# ButtonHighlight.net
KiCad netlist of a schematic drawn in EAGLE
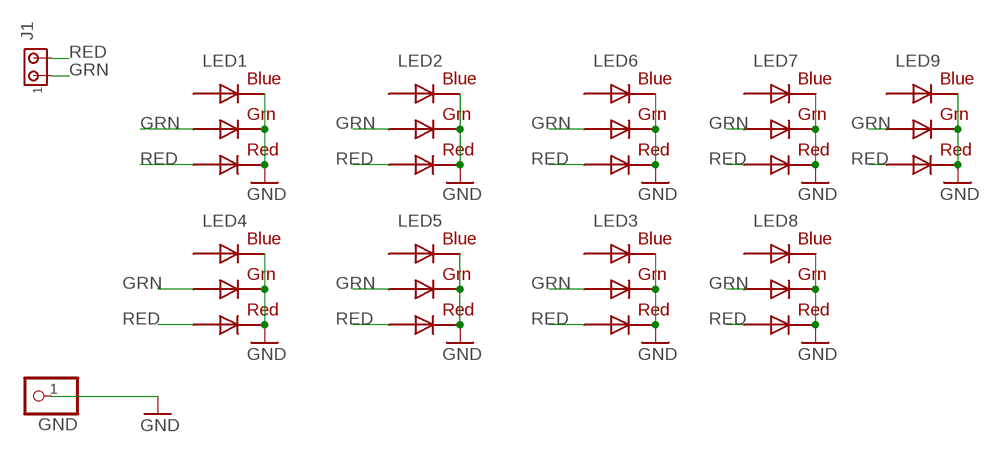
[diagram p0: schematic, sheet 1]

(export (version "E")
  (design (tool "Eeschema 10.0.6"))
  (components
    (comp (ref "GND")
      (value "PINHD-1X1")
      (footprint "eagle-import:1X01")
      (libsource (lib "eagle-import") (part "PINHD-1X1"))
    )
    (comp (ref "J1")
      (value "MTA02-100")
      (footprint "eagle-import:10X02MTA")
      (libsource (lib "eagle-import") (part "MTA02-100"))
    )
    (comp (ref "LED1")
      (value "RGBLED5050")
      (footprint "eagle-import:RGBLED5050")
      (libsource (lib "eagle-import") (part "RGBLED5050"))
    )
    (comp (ref "LED2")
      (value "RGBLED5050")
      (footprint "eagle-import:RGBLED5050")
      (libsource (lib "eagle-import") (part "RGBLED5050"))
    )
    (comp (ref "LED3")
      (value "RGBLED5050")
      (footprint "eagle-import:RGBLED5050")
      (libsource (lib "eagle-import") (part "RGBLED5050"))
    )
    (comp (ref "LED4")
      (value "RGBLED5050")
      (footprint "eagle-import:RGBLED5050")
      (libsource (lib "eagle-import") (part "RGBLED5050"))
    )
    (comp (ref "LED5")
      (value "RGBLED5050")
      (footprint "eagle-import:RGBLED5050")
      (libsource (lib "eagle-import") (part "RGBLED5050"))
    )
    (comp (ref "LED6")
      (value "RGBLED5050")
      (footprint "eagle-import:RGBLED5050")
      (libsource (lib "eagle-import") (part "RGBLED5050"))
    )
    (comp (ref "LED7")
      (value "RGBLED5050")
      (footprint "eagle-import:RGBLED5050")
      (libsource (lib "eagle-import") (part "RGBLED5050"))
    )
    (comp (ref "LED8")
      (value "RGBLED5050")
      (footprint "eagle-import:RGBLED5050")
      (libsource (lib "eagle-import") (part "RGBLED5050"))
    )
    (comp (ref "LED9")
      (value "RGBLED5050")
      (footprint "eagle-import:RGBLED5050")
      (libsource (lib "eagle-import") (part "RGBLED5050"))
    )
  )
  (nets
    (net (code "1") (name "/GRN") (class "Default")
      (node (ref "J1") (pin "1") (pinfunction "1_1") (pintype "passive"))
      (node (ref "LED1") (pin "1") (pinfunction "GREEN_A_1") (pintype "bidirectional"))
      (node (ref "LED2") (pin "1") (pinfunction "GREEN_A_1") (pintype "bidirectional"))
      (node (ref "LED3") (pin "1") (pinfunction "GREEN_A_1") (pintype "bidirectional"))
      (node (ref "LED4") (pin "1") (pinfunction "GREEN_A_1") (pintype "bidirectional"))
      (node (ref "LED5") (pin "1") (pinfunction "GREEN_A_1") (pintype "bidirectional"))
      (node (ref "LED6") (pin "1") (pinfunction "GREEN_A_1") (pintype "bidirectional"))
      (node (ref "LED7") (pin "1") (pinfunction "GREEN_A_1") (pintype "bidirectional"))
      (node (ref "LED8") (pin "1") (pinfunction "GREEN_A_1") (pintype "bidirectional"))
      (node (ref "LED9") (pin "1") (pinfunction "GREEN_A_1") (pintype "bidirectional"))
    )
    (net (code "2") (name "/RED") (class "Default")
      (node (ref "J1") (pin "2") (pinfunction "2_2") (pintype "passive"))
      (node (ref "LED1") (pin "2") (pinfunction "RED_A_2") (pintype "bidirectional"))
      (node (ref "LED2") (pin "2") (pinfunction "RED_A_2") (pintype "bidirectional"))
      (node (ref "LED3") (pin "2") (pinfunction "RED_A_2") (pintype "bidirectional"))
      (node (ref "LED4") (pin "2") (pinfunction "RED_A_2") (pintype "bidirectional"))
      (node (ref "LED5") (pin "2") (pinfunction "RED_A_2") (pintype "bidirectional"))
      (node (ref "LED6") (pin "2") (pinfunction "RED_A_2") (pintype "bidirectional"))
      (node (ref "LED7") (pin "2") (pinfunction "RED_A_2") (pintype "bidirectional"))
      (node (ref "LED8") (pin "2") (pinfunction "RED_A_2") (pintype "bidirectional"))
      (node (ref "LED9") (pin "2") (pinfunction "RED_A_2") (pintype "bidirectional"))
    )
    (net (code "3") (name "GND") (class "Default")
      (node (ref "GND") (pin "1") (pinfunction "1_1") (pintype "passive"))
      (node (ref "LED1") (pin "4") (pinfunction "BLUE_C_4") (pintype "bidirectional"))
      (node (ref "LED1") (pin "5") (pinfunction "RED_C_5") (pintype "bidirectional"))
      (node (ref "LED1") (pin "6") (pinfunction "GREEN_C_6") (pintype "bidirectional"))
      (node (ref "LED2") (pin "4") (pinfunction "BLUE_C_4") (pintype "bidirectional"))
      (node (ref "LED2") (pin "5") (pinfunction "RED_C_5") (pintype "bidirectional"))
      (node (ref "LED2") (pin "6") (pinfunction "GREEN_C_6") (pintype "bidirectional"))
      (node (ref "LED3") (pin "4") (pinfunction "BLUE_C_4") (pintype "bidirectional"))
      (node (ref "LED3") (pin "5") (pinfunction "RED_C_5") (pintype "bidirectional"))
      (node (ref "LED3") (pin "6") (pinfunction "GREEN_C_6") (pintype "bidirectional"))
      (node (ref "LED4") (pin "4") (pinfunction "BLUE_C_4") (pintype "bidirectional"))
      (node (ref "LED4") (pin "5") (pinfunction "RED_C_5") (pintype "bidirectional"))
      (node (ref "LED4") (pin "6") (pinfunction "GREEN_C_6") (pintype "bidirectional"))
      (node (ref "LED5") (pin "4") (pinfunction "BLUE_C_4") (pintype "bidirectional"))
      (node (ref "LED5") (pin "5") (pinfunction "RED_C_5") (pintype "bidirectional"))
      (node (ref "LED5") (pin "6") (pinfunction "GREEN_C_6") (pintype "bidirectional"))
      (node (ref "LED6") (pin "4") (pinfunction "BLUE_C_4") (pintype "bidirectional"))
      (node (ref "LED6") (pin "5") (pinfunction "RED_C_5") (pintype "bidirectional"))
      (node (ref "LED6") (pin "6") (pinfunction "GREEN_C_6") (pintype "bidirectional"))
      (node (ref "LED7") (pin "4") (pinfunction "BLUE_C_4") (pintype "bidirectional"))
      (node (ref "LED7") (pin "5") (pinfunction "RED_C_5") (pintype "bidirectional"))
      (node (ref "LED7") (pin "6") (pinfunction "GREEN_C_6") (pintype "bidirectional"))
      (node (ref "LED8") (pin "4") (pinfunction "BLUE_C_4") (pintype "bidirectional"))
      (node (ref "LED8") (pin "5") (pinfunction "RED_C_5") (pintype "bidirectional"))
      (node (ref "LED8") (pin "6") (pinfunction "GREEN_C_6") (pintype "bidirectional"))
      (node (ref "LED9") (pin "4") (pinfunction "BLUE_C_4") (pintype "bidirectional"))
      (node (ref "LED9") (pin "5") (pinfunction "RED_C_5") (pintype "bidirectional"))
      (node (ref "LED9") (pin "6") (pinfunction "GREEN_C_6") (pintype "bidirectional"))
    )
    (net (code "4") (name "unconnected-(LED1-BLUE_A-Pad3)") (class "Default")
      (node (ref "LED1") (pin "3") (pinfunction "BLUE_A_3") (pintype "bidirectional"))
    )
    (net (code "5") (name "unconnected-(LED2-BLUE_A-Pad3)") (class "Default")
      (node (ref "LED2") (pin "3") (pinfunction "BLUE_A_3") (pintype "bidirectional"))
    )
    (net (code "6") (name "unconnected-(LED3-BLUE_A-Pad3)") (class "Default")
      (node (ref "LED3") (pin "3") (pinfunction "BLUE_A_3") (pintype "bidirectional"))
    )
    (net (code "7") (name "unconnected-(LED4-BLUE_A-Pad3)") (class "Default")
      (node (ref "LED4") (pin "3") (pinfunction "BLUE_A_3") (pintype "bidirectional"))
    )
    (net (code "8") (name "unconnected-(LED5-BLUE_A-Pad3)") (class "Default")
      (node (ref "LED5") (pin "3") (pinfunction "BLUE_A_3") (pintype "bidirectional"))
    )
    (net (code "9") (name "unconnected-(LED6-BLUE_A-Pad3)") (class "Default")
      (node (ref "LED6") (pin "3") (pinfunction "BLUE_A_3") (pintype "bidirectional"))
    )
    (net (code "10") (name "unconnected-(LED7-BLUE_A-Pad3)") (class "Default")
      (node (ref "LED7") (pin "3") (pinfunction "BLUE_A_3") (pintype "bidirectional"))
    )
    (net (code "11") (name "unconnected-(LED8-BLUE_A-Pad3)") (class "Default")
      (node (ref "LED8") (pin "3") (pinfunction "BLUE_A_3") (pintype "bidirectional"))
    )
    (net (code "12") (name "unconnected-(LED9-BLUE_A-Pad3)") (class "Default")
      (node (ref "LED9") (pin "3") (pinfunction "BLUE_A_3") (pintype "bidirectional"))
    )
  )
)
